# Sheet1.net
KiCad netlist of a schematic drawn in Altium Designer
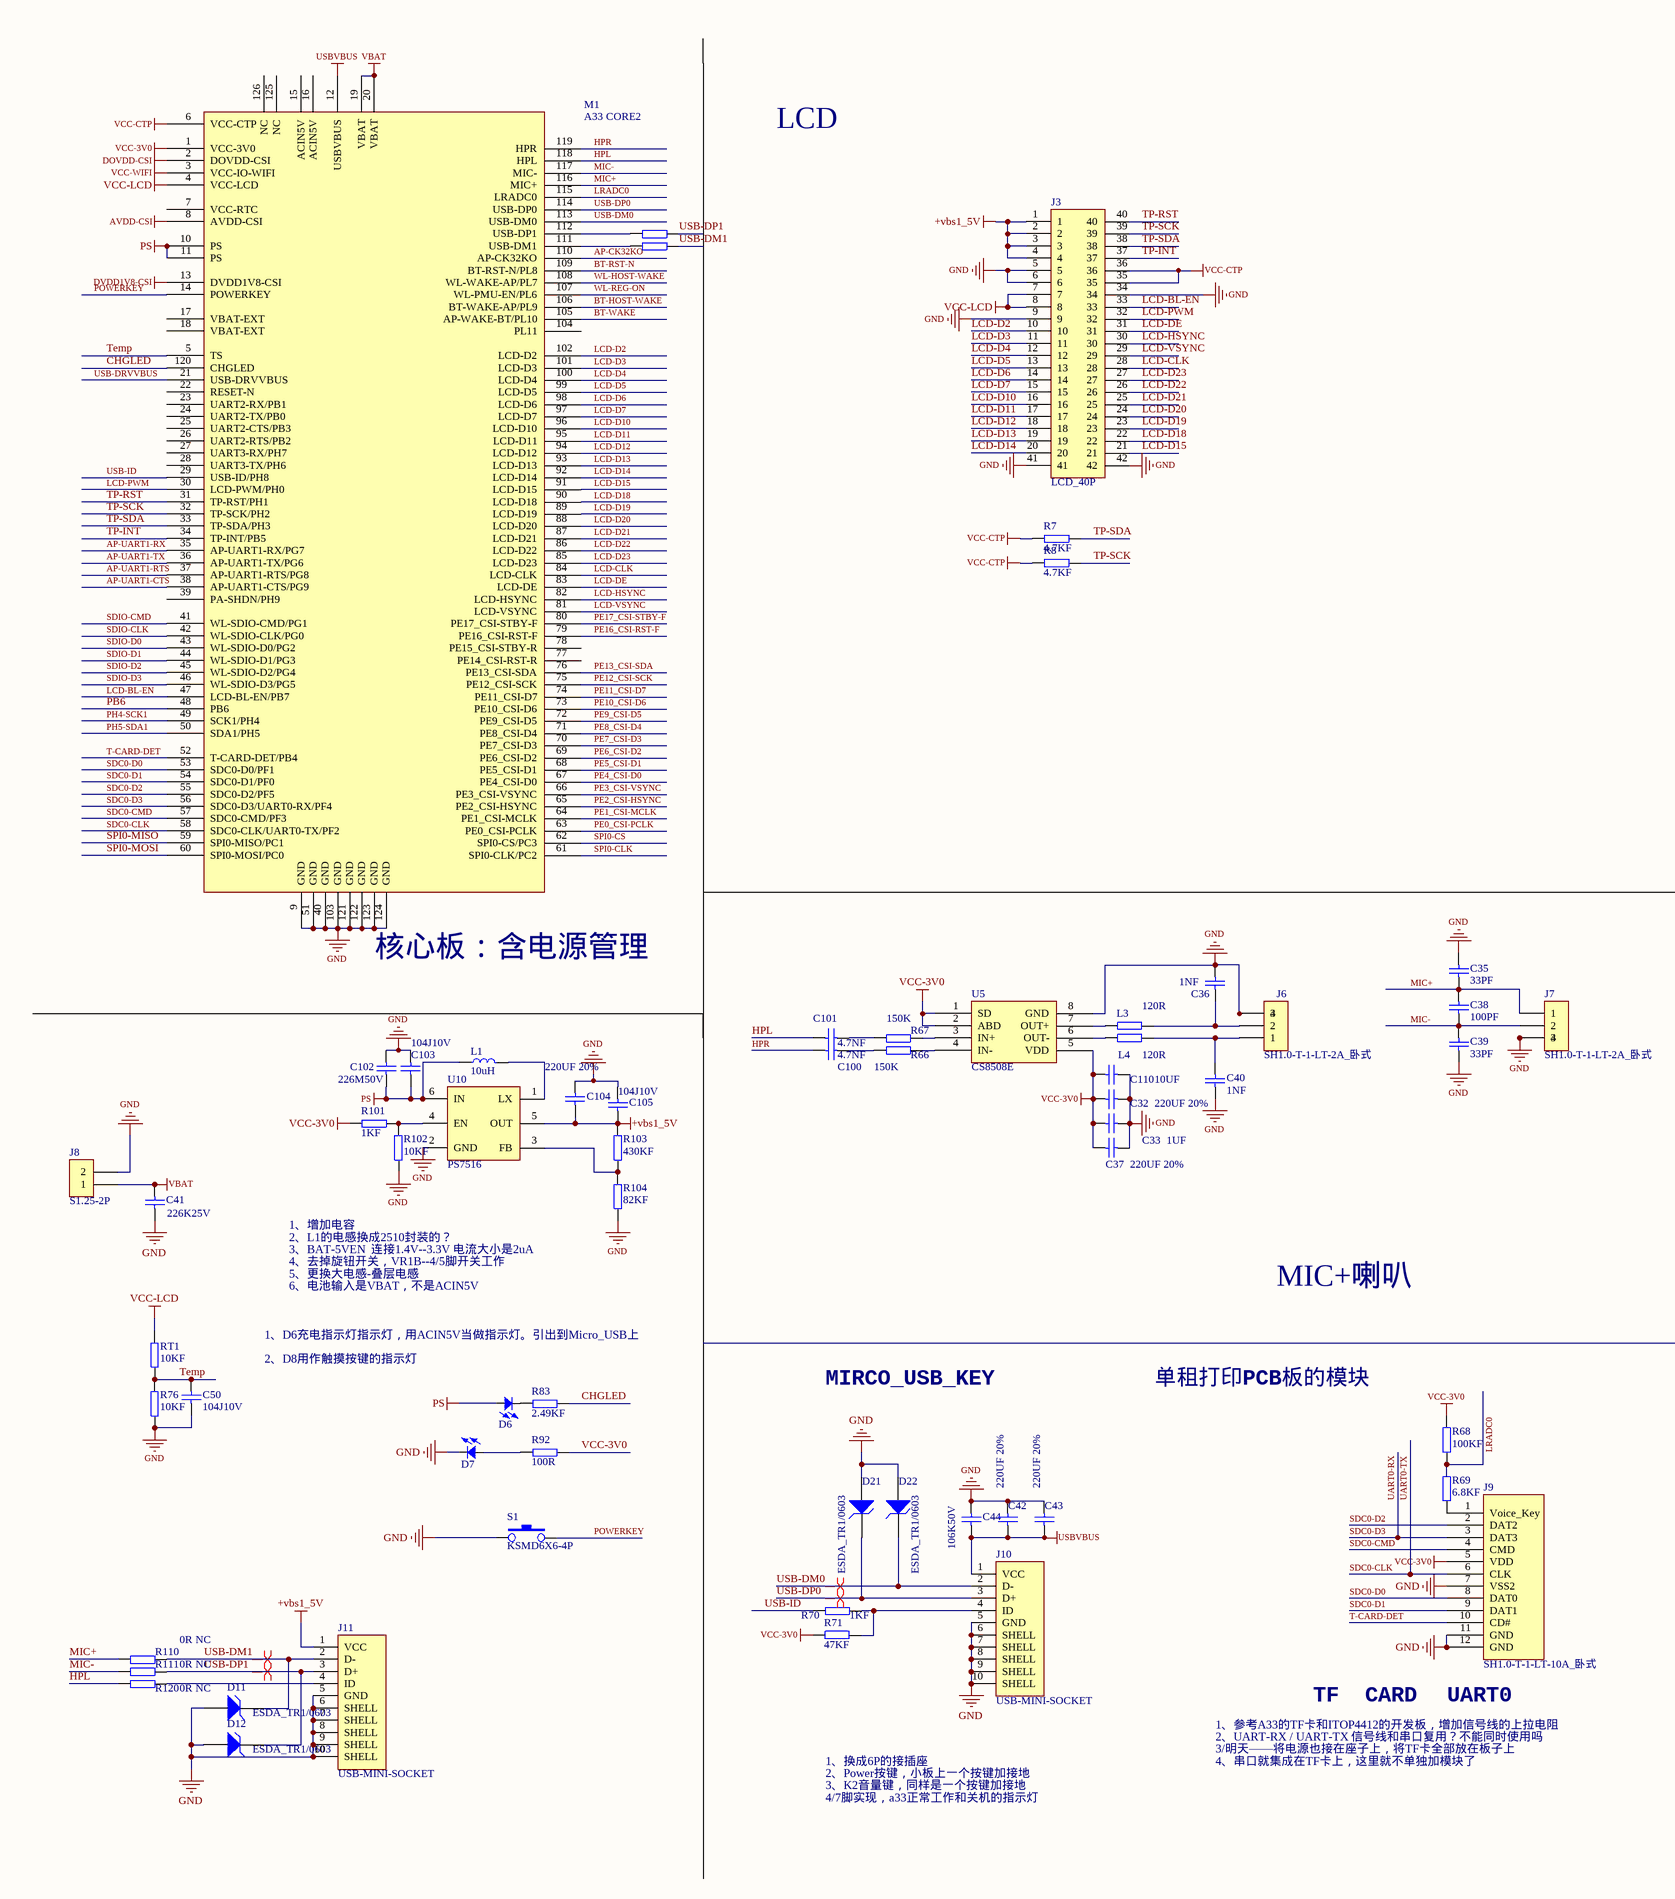
[diagram p0: Sheet1.SchDoc, left]
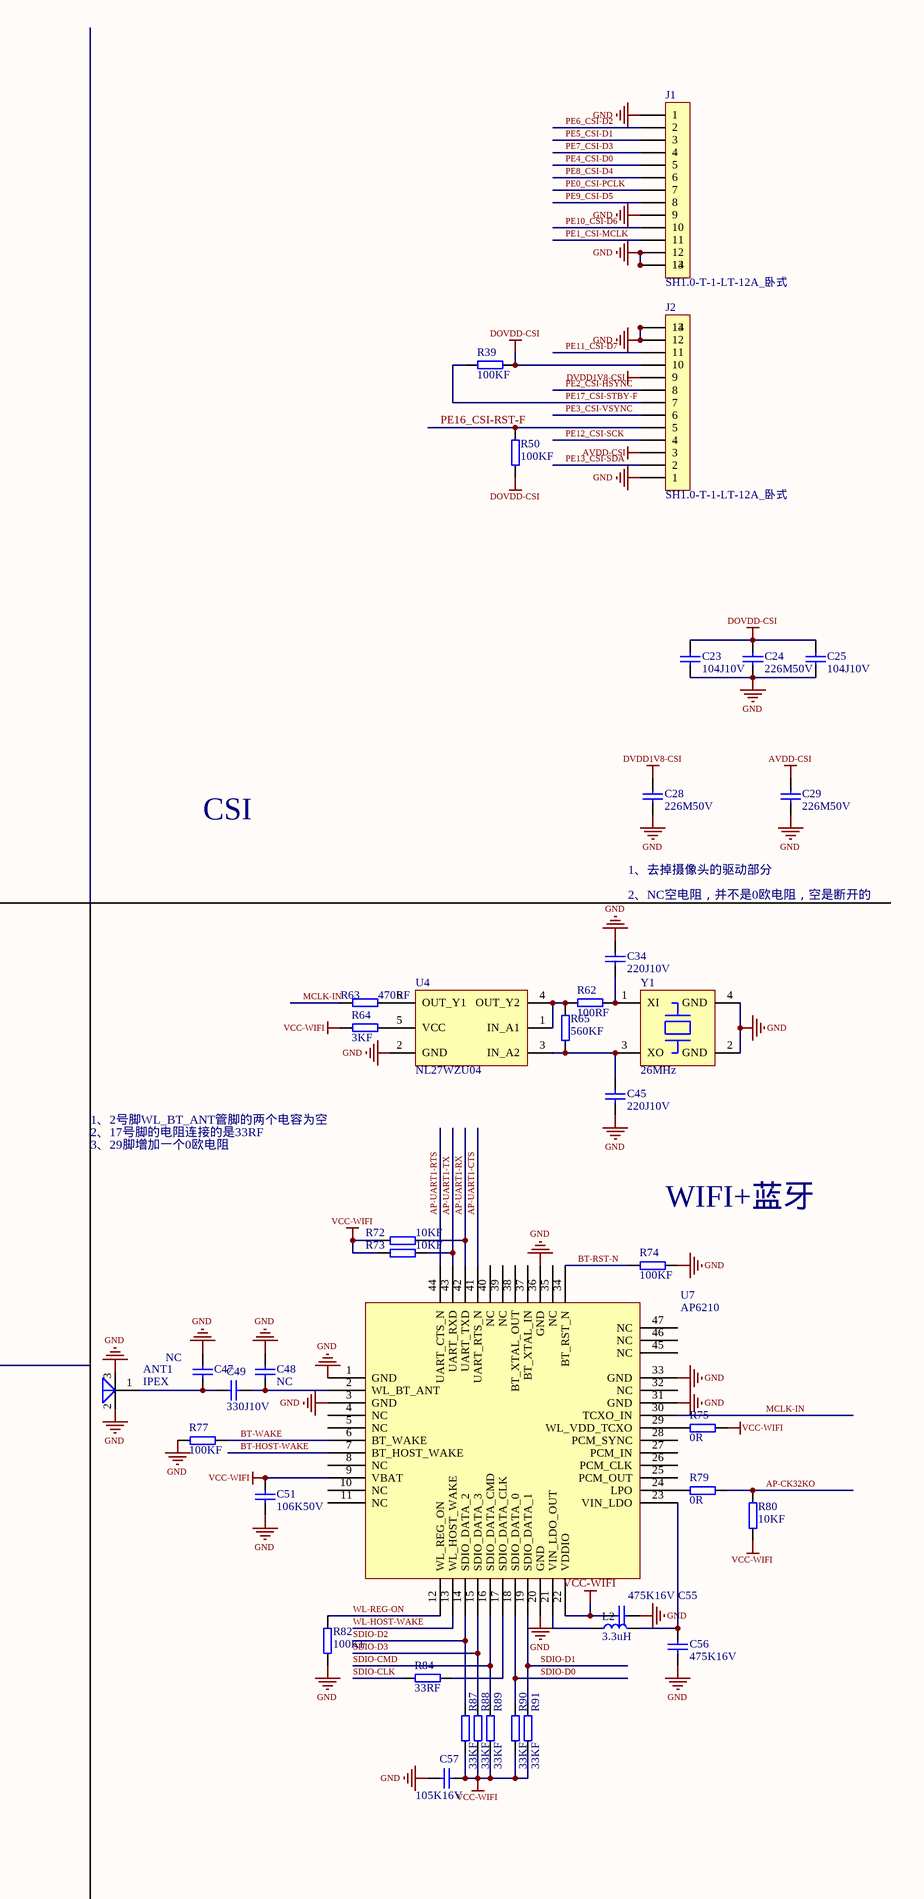
[diagram p1: Sheet1.SchDoc, right]

(export (version "E")
  (design (tool "Eeschema 10.0.6"))
  (components
    (comp (ref "ANT1")
      (value "IPEX")
      (footprint "J-IPEX")
      (description "天线接口IPEX")
      (libsource (lib "Connector") (part "J-IPEX"))
    )
    (comp (ref "C23")
      (value "104J10V")
      (footprint "C0402")
      (description "贴片电容-陶瓷")
      (libsource (lib "Capacitor") (part "C0402X7R-104J10V"))
    )
    (comp (ref "C24")
      (value "226M50V")
      (footprint "C0805")
      (description "贴片电容-陶瓷")
      (libsource (lib "Capacitor") (part "C0805Y5V-226M50V"))
    )
    (comp (ref "C25")
      (value "104J10V")
      (footprint "C0402")
      (description "贴片电容-陶瓷")
      (libsource (lib "Capacitor") (part "C0402X7R-104J10V"))
    )
    (comp (ref "C28")
      (value "226M50V")
      (footprint "C0805")
      (description "贴片电容-陶瓷")
      (libsource (lib "Capacitor") (part "C0805Y5V-226M50V"))
    )
    (comp (ref "C29")
      (value "226M50V")
      (footprint "C0805")
      (description "贴片电容-陶瓷")
      (libsource (lib "Capacitor") (part "C0805Y5V-226M50V"))
    )
    (comp (ref "C32")
      (value "220UF 20%")
      (footprint "C1206")
      (description "C 1206钽电容 --220UF 10V 3216 A型 有极性电容 3.2mm X 1.6mm")
      (libsource (lib "Capacitor") (part "C1206-A型 极性电容"))
    )
    (comp (ref "C33")
      (value "1UF")
      (footprint "C0402")
      (description "贴片电容-陶瓷")
      (libsource (lib "Capacitor") (part "C0402X7R-105J10V"))
    )
    (comp (ref "C34")
      (value "220J10V")
      (footprint "C0402")
      (description "贴片电容-陶瓷")
      (libsource (lib "Capacitor") (part "C0402X7R-220J10V"))
    )
    (comp (ref "C35")
      (value "33PF")
      (footprint "C0402")
      (description "贴片电容-陶瓷")
      (libsource (lib "Capacitor") (part "C0402X7R-104J10V"))
    )
    (comp (ref "C36")
      (value "1NF")
      (footprint "C0402")
      (description "贴片电容-陶瓷")
      (libsource (lib "Capacitor") (part "C0402X7R-220J10V"))
    )
    (comp (ref "C37")
      (value "220UF 20%")
      (footprint "C1206")
      (description "C 1206钽电容 --220UF 10V 3216 A型 有极性电容 3.2mm X 1.6mm")
      (libsource (lib "Capacitor") (part "C1206-A型 极性电容"))
    )
    (comp (ref "C38")
      (value "100PF")
      (footprint "C0402")
      (description "贴片电容-陶瓷")
      (libsource (lib "Capacitor") (part "C0402X7R-104J10V"))
    )
    (comp (ref "C39")
      (value "33PF")
      (footprint "C0402")
      (description "贴片电容-陶瓷")
      (libsource (lib "Capacitor") (part "C0402X7R-104J10V"))
    )
    (comp (ref "C40")
      (value "1NF")
      (footprint "C0402")
      (description "贴片电容-陶瓷")
      (libsource (lib "Capacitor") (part "C0402X7R-220J10V"))
    )
    (comp (ref "C41")
      (value "226K25V")
      (footprint "C0805")
      (description "贴片电容-陶瓷")
      (libsource (lib "Capacitor") (part "C0805X7R-226K25V"))
    )
    (comp (ref "C42")
      (value "220UF 20%")
      (footprint "C1206")
      (description "C 1206钽电容 --220UF 10V 3216 A型 有极性电容 3.2mm X 1.6mm")
      (libsource (lib "Capacitor") (part "C1206-A型 极性电容"))
    )
    (comp (ref "C43")
      (value "220UF 20%")
      (footprint "C1206")
      (description "C 1206钽电容 --220UF 10V 3216 A型 有极性电容 3.2mm X 1.6mm")
      (libsource (lib "Capacitor") (part "C1206-A型 极性电容"))
    )
    (comp (ref "C44")
      (value "106K50V")
      (footprint "C0603")
      (description "贴片电容-陶瓷")
      (libsource (lib "Capacitor") (part "C0603X7R-106K50V"))
    )
    (comp (ref "C45")
      (value "220J10V")
      (footprint "C0402")
      (description "贴片电容-陶瓷")
      (libsource (lib "Capacitor") (part "C0402X7R-220J10V"))
    )
    (comp (ref "C47")
      (value "NC")
      (footprint "C0402")
      (description "贴片电容-陶瓷")
      (libsource (lib "Capacitor") (part "C0402X7R-220J10V"))
    )
    (comp (ref "C48")
      (value "NC")
      (footprint "C0402")
      (description "贴片电容-陶瓷")
      (libsource (lib "Capacitor") (part "C0402X7R-220J10V"))
    )
    (comp (ref "C49")
      (value "330J10V")
      (footprint "C0402")
      (description "贴片电容-陶瓷")
      (libsource (lib "Capacitor") (part "C0402X7R-330J10V"))
    )
    (comp (ref "C50")
      (value "104J10V")
      (footprint "C0402")
      (description "贴片电容-陶瓷")
      (libsource (lib "Capacitor") (part "C0402X7R-104J10V"))
    )
    (comp (ref "C51")
      (value "106K50V")
      (footprint "C0603")
      (description "贴片电容-陶瓷")
      (libsource (lib "Capacitor") (part "C0603X7R-106K50V"))
    )
    (comp (ref "C55")
      (value "475K16V")
      (footprint "C0603")
      (description "贴片电容-陶瓷")
      (libsource (lib "Capacitor") (part "C0603X7R-475K16V"))
    )
    (comp (ref "C56")
      (value "475K16V")
      (footprint "C0603")
      (description "贴片电容-陶瓷")
      (libsource (lib "Capacitor") (part "C0603X7R-475K16V"))
    )
    (comp (ref "C57")
      (value "105K16V")
      (footprint "C0603")
      (description "贴片电容-陶瓷")
      (libsource (lib "Capacitor") (part "C0603X7R-105K16V"))
    )
    (comp (ref "C100")
      (value "4.7NF")
      (footprint "C0603")
      (description "贴片电容-陶瓷")
      (libsource (lib "Capacitor") (part "C0603X7R-330J25V"))
    )
    (comp (ref "C101")
      (value "4.7NF")
      (footprint "C0603")
      (description "贴片电容-陶瓷")
      (libsource (lib "Capacitor") (part "C0603X7R-330J25V"))
    )
    (comp (ref "C102")
      (value "226M50V")
      (footprint "C0805")
      (description "贴片电容-陶瓷")
      (libsource (lib "Capacitor") (part "C0805Y5V-226M50V"))
    )
    (comp (ref "C103")
      (value "104J10V")
      (footprint "C0402")
      (description "贴片电容-陶瓷")
      (libsource (lib "Capacitor") (part "C0402X7R-104J10V"))
    )
    (comp (ref "C104")
      (value "220UF 20%")
      (footprint "C1206")
      (description "C 1206钽电容 --220UF 10V 3216 A型 有极性电容 3.2mm X 1.6mm")
      (libsource (lib "Capacitor") (part "C1206-A型 极性电容"))
    )
    (comp (ref "C105")
      (value "104J10V")
      (footprint "C0402")
      (description "贴片电容-陶瓷")
      (libsource (lib "Capacitor") (part "C0402X7R-104J10V"))
    )
    (comp (ref "C110")
      (value "10UF")
      (footprint "C0603")
      (description "贴片电容-陶瓷")
      (libsource (lib "Capacitor") (part "C0603X7R-330J25V"))
    )
    (comp (ref "D6") (value "发光二极管") (footprint "PCB11:LEDΦ5-H12") (libsource (lib "1_1") (part "发光二极管")))
    (comp (ref "D7") (value "发光二极管") (footprint "PCB11:LEDΦ5-H12") (libsource (lib "1_1") (part "发光二极管")))
    (comp (ref "D11")
      (value "ESDA_TR1/0603")
      (footprint "HS_0603D")
      (description "Zener Diode")
      (fields (field (name "PUBLISHER") "*"))
      (libsource (lib "HSC32K1(QFN56)_BlueTooth_V2.0_20171108 - 副本") (part "D Zener"))
    )
    (comp (ref "D12")
      (value "ESDA_TR1/0603")
      (footprint "HS_0603D")
      (description "Zener Diode")
      (fields (field (name "PUBLISHER") "*"))
      (libsource (lib "HSC32K1(QFN56)_BlueTooth_V2.0_20171108 - 副本") (part "D Zener"))
    )
    (comp (ref "D21")
      (value "ESDA_TR1/0603")
      (footprint "HS_0603D")
      (description "Zener Diode")
      (fields (field (name "PUBLISHER") "*"))
      (libsource (lib "1_1") (part "D Zener"))
    )
    (comp (ref "D22")
      (value "ESDA_TR1/0603")
      (footprint "HS_0603D")
      (description "Zener Diode")
      (fields (field (name "PUBLISHER") "*"))
      (libsource (lib "1_1") (part "D Zener"))
    )
    (comp (ref "J1")
      (value "SH1.0-T-1-LT-12A_卧式")
      (footprint "J-SH1.0-T-1-LT-12A_卧式")
      (libsource (lib "") (part "SH1.0-T-1-LT-12A_卧式_1"))
    )
    (comp (ref "J2")
      (value "SH1.0-T-1-LT-12A_卧式")
      (footprint "J-SH1.0-T-1-LT-12A_卧式")
      (libsource (lib "Connector") (part "SH1.0-T-1-LT-12A_卧式"))
    )
    (comp (ref "J3") (value "LCD_40P") (footprint "LCD P40") (libsource (lib "Connector") (part "LCD_40P")))
    (comp (ref "J6")
      (value "SH1.0-T-1-LT-2A_卧式")
      (footprint "J-SH1.0-T-1-LT-2A_卧式")
      (libsource (lib "") (part "SH1.0-T-1-LT-2A_卧式_1"))
    )
    (comp (ref "J7")
      (value "SH1.0-T-1-LT-2A_卧式")
      (footprint "J-SH1.0-T-1-LT-2A_卧式")
      (libsource (lib "Connector") (part "SH1.0-T-1-LT-2A_卧式"))
    )
    (comp (ref "J8")
      (value "S1.25-2P")
      (footprint "PCB11:S1.25-2P")
      (description "定制铜排")
      (libsource (lib "Others") (part "O-CP-840-2P"))
    )
    (comp (ref "J9")
      (value "SH1.0-T-1-LT-10A_卧式")
      (footprint "J-SH1.0-T-1-LT-10A_卧式")
      (libsource (lib "Connector") (part "SH1.0-T-1-LT-10A_卧式"))
    )
    (comp (ref "J10")
      (value "USB-MINI-SOCKET")
      (footprint "MICRO-USB - 5.9")
      (description "USB-A卧式插座")
      (libsource (lib "Connector") (part "J-USB-MINI-SOCKET"))
    )
    (comp (ref "J11")
      (value "USB-MINI-SOCKET")
      (footprint "MICRO-USB - 5.9")
      (description "USB-A卧式插座")
      (libsource (lib "Connector") (part "J-USB-MINI-SOCKET"))
    )
    (comp (ref "L1")
      (value "10uH")
      (footprint "L-2520")
      (description "贴片电感-层叠")
      (libsource (lib "magnetic") (part "L-2520-10uH"))
    )
    (comp (ref "L2")
      (value "3.3uH")
      (footprint "L0805")
      (description "贴片电感-层叠")
      (libsource (lib "magnetic") (part "L-0805-3.3uH"))
    )
    (comp (ref "L3")
      (value "120R")
      (footprint "R0603")
      (description "贴片电阻-通用")
      (libsource (lib "Resistor") (part "R0603-47KF"))
    )
    (comp (ref "L4")
      (value "120R")
      (footprint "R0603")
      (description "贴片电阻-通用")
      (libsource (lib "Resistor") (part "R0603-47KF"))
    )
    (comp (ref "M1")
      (value "A33 CORE2")
      (footprint "AIWAC-bolster-V02:A33-CORE2")
      (libsource (lib "Module") (part "A33 CORE2"))
    )
    (comp (ref "R7")
      (value "4.7KF")
      (footprint "R0402")
      (description "贴片电阻-通用")
      (libsource (lib "Resistor") (part "R0402-4.7KF"))
    )
    (comp (ref "R8")
      (value "4.7KF")
      (footprint "R0402")
      (description "贴片电阻-通用")
      (libsource (lib "Resistor") (part "R0402-4.7KF"))
    )
    (comp (ref "R39")
      (value "100KF")
      (footprint "R0603")
      (description "贴片电阻-通用")
      (libsource (lib "Resistor") (part "R0603-100KF"))
    )
    (comp (ref "R50")
      (value "100KF")
      (footprint "R0603")
      (description "贴片电阻-通用")
      (libsource (lib "Resistor") (part "R0603-100KF"))
    )
    (comp (ref "R62")
      (value "100RF")
      (footprint "R0603")
      (description "贴片电阻-通用")
      (libsource (lib "Resistor") (part "R0603-100RF"))
    )
    (comp (ref "R63")
      (value "470RF")
      (footprint "R0603")
      (description "贴片电阻-通用")
      (libsource (lib "Resistor") (part "R0603-470RF"))
    )
    (comp (ref "R64")
      (value "3KF")
      (footprint "R0603")
      (description "贴片电阻-通用")
      (libsource (lib "Resistor") (part "R0603-3KF"))
    )
    (comp (ref "R65")
      (value "560KF")
      (footprint "R0603")
      (description "贴片电阻-通用")
      (libsource (lib "Resistor") (part "R0603-560KF"))
    )
    (comp (ref "R66")
      (value "150K")
      (footprint "R0603")
      (description "贴片电阻-通用")
      (libsource (lib "Resistor") (part "R0603-10KF"))
    )
    (comp (ref "R67")
      (value "150K")
      (footprint "R0603")
      (description "贴片电阻-通用")
      (libsource (lib "Resistor") (part "R0603-10KF"))
    )
    (comp (ref "R68")
      (value "100KF")
      (footprint "R0603")
      (description "贴片电阻-通用")
      (libsource (lib "Resistor") (part "R0603-100KF"))
    )
    (comp (ref "R69")
      (value "6.8KF")
      (footprint "R0603")
      (description "贴片电阻-通用")
      (libsource (lib "Resistor") (part "R0603-6.8KF"))
    )
    (comp (ref "R70")
      (value "1KF")
      (footprint "R0603")
      (description "贴片电阻-通用")
      (libsource (lib "Resistor") (part "R0603-1KF"))
    )
    (comp (ref "R71")
      (value "47KF")
      (footprint "R0603")
      (description "贴片电阻-通用")
      (libsource (lib "Resistor") (part "R0603-47KF"))
    )
    (comp (ref "R72")
      (value "10KF")
      (footprint "R0603")
      (description "贴片电阻-通用")
      (libsource (lib "Resistor") (part "R0603-10KF"))
    )
    (comp (ref "R73")
      (value "10KF")
      (footprint "R0603")
      (description "贴片电阻-通用")
      (libsource (lib "Resistor") (part "R0603-10KF"))
    )
    (comp (ref "R74")
      (value "100KF")
      (footprint "R0603")
      (description "贴片电阻-通用")
      (libsource (lib "Resistor") (part "R0603-100KF"))
    )
    (comp (ref "R75")
      (value "0R")
      (footprint "R0603")
      (description "贴片电阻-通用")
      (libsource (lib "Resistor") (part "R0603-0R"))
    )
    (comp (ref "R76")
      (value "10KF")
      (footprint "R0603")
      (description "贴片电阻-通用")
      (libsource (lib "Resistor") (part "R0603-10KF"))
    )
    (comp (ref "R77")
      (value "100KF")
      (footprint "R0603")
      (description "贴片电阻-通用")
      (libsource (lib "Resistor") (part "R0603-100KF"))
    )
    (comp (ref "R79")
      (value "0R")
      (footprint "R0603")
      (description "贴片电阻-通用")
      (libsource (lib "Resistor") (part "R0603-0R"))
    )
    (comp (ref "R80")
      (value "10KF")
      (footprint "R0603")
      (description "贴片电阻-通用")
      (libsource (lib "Resistor") (part "R0603-10KF"))
    )
    (comp (ref "R82")
      (value "100KF")
      (footprint "R0603")
      (description "贴片电阻-通用")
      (libsource (lib "Resistor") (part "R0603-100KF"))
    )
    (comp (ref "R83")
      (value "2.49KF")
      (footprint "R0603")
      (description "贴片电阻-通用")
      (libsource (lib "Resistor") (part "R0603-3KF"))
    )
    (comp (ref "R84")
      (value "33RF")
      (footprint "R0603")
      (description "贴片电阻-通用")
      (libsource (lib "Resistor") (part "R0603-33RF"))
    )
    (comp (ref "R87")
      (value "33KF")
      (footprint "R0603")
      (description "贴片电阻-通用")
      (libsource (lib "Resistor") (part "R0603-33KF"))
    )
    (comp (ref "R88")
      (value "33KF")
      (footprint "R0603")
      (description "贴片电阻-通用")
      (libsource (lib "Resistor") (part "R0603-33KF"))
    )
    (comp (ref "R89")
      (value "33KF")
      (footprint "R0603")
      (description "贴片电阻-通用")
      (libsource (lib "Resistor") (part "R0603-33KF"))
    )
    (comp (ref "R90")
      (value "33KF")
      (footprint "R0603")
      (description "贴片电阻-通用")
      (libsource (lib "Resistor") (part "R0603-33KF"))
    )
    (comp (ref "R91")
      (value "33KF")
      (footprint "R0603")
      (description "贴片电阻-通用")
      (libsource (lib "Resistor") (part "R0603-33KF"))
    )
    (comp (ref "R92")
      (value "100R")
      (footprint "R0603")
      (description "贴片电阻-通用")
      (libsource (lib "Resistor") (part "R0603-2KF"))
    )
    (comp (ref "R101")
      (value "1KF")
      (footprint "R0603")
      (description "贴片电阻-通用")
      (libsource (lib "Resistor") (part "R0603-1KF"))
    )
    (comp (ref "R102")
      (value "10KF")
      (footprint "R0603")
      (description "贴片电阻-通用")
      (libsource (lib "Resistor") (part "R0603-10KF"))
    )
    (comp (ref "R103")
      (value "430KF")
      (footprint "R0603")
      (description "贴片电阻-通用")
      (libsource (lib "Resistor") (part "R0603-430KF"))
    )
    (comp (ref "R104")
      (value "82KF")
      (footprint "R0603")
      (description "贴片电阻-通用")
      (libsource (lib "Resistor") (part "R0603-82KF"))
    )
    (comp (ref "R110")
      (value "0R NC")
      (footprint "R0603")
      (description "贴片电阻-通用")
      (libsource (lib "Resistor") (part "R0603-2KF"))
    )
    (comp (ref "R111")
      (value "0R NC")
      (footprint "R0603")
      (description "贴片电阻-通用")
      (libsource (lib "Resistor") (part "R0603-2KF"))
    )
    (comp (ref "R112")
      (value "0R  NC")
      (footprint "R0603")
      (description "贴片电阻-通用")
      (libsource (lib "Resistor") (part "R0603-10KF"))
    )
    (comp (ref "R113")
      (value "0R  NC")
      (footprint "R0603")
      (description "贴片电阻-通用")
      (libsource (lib "Resistor") (part "R0603-10KF"))
    )
    (comp (ref "R120")
      (value "0R NC")
      (footprint "R0603")
      (description "贴片电阻-通用")
      (libsource (lib "Resistor") (part "R0603-2KF"))
    )
    (comp (ref "RT1")
      (value "10KF")
      (footprint "XU-GENARAL PCB :0402")
      (description "贴片电阻-通用")
      (libsource (lib "Resistor") (part "R0603-10KF"))
    )
    (comp (ref "S1")
      (value "KSMD6X6-4P")
      (footprint "PCB11:SW2-6*6H")
      (description "轻触按键")
      (libsource (lib "Key") (part "S-KSMD6X6-4P"))
    )
    (comp (ref "U4") (value "NL27WZU04") (footprint "U-TSOP-6") (libsource (lib "IC") (part "NL27WZU04")))
    (comp (ref "U5") (value "CS8508E") (footprint "SO-8") (libsource (lib "PCB_Project_1") (part "CS8508E")))
    (comp (ref "U7")
      (value "AP6210")
      (footprint "AIWAC-bolster-V02:AP6210")
      (libsource (lib "IC") (part "AP6210"))
    )
    (comp (ref "U10") (value "PS7516") (footprint "U-SOT-23-6") (libsource (lib "IC") (part "PS7516")))
    (comp (ref "Y1")
      (value "26MHz")
      (footprint "Y-CPX-32GA-4P")
      (description "晶振-贴片无源")
      (libsource (lib "Others") (part "YC-26MHz"))
    )
  )
  (nets
    (net (code "1") (name "+vbs1_5V") (class "Default")
      (node (ref "C104") (pin "1") (pinfunction "1_1") (pintype "passive"))
      (node (ref "C105") (pin "2") (pinfunction "2_2") (pintype "passive"))
      (node (ref "J11") (pin "1") (pinfunction "VCC_1") (pintype "passive"))
      (node (ref "J3") (pin "1") (pinfunction "1_1") (pintype "passive"))
      (node (ref "J3") (pin "2") (pinfunction "2_2") (pintype "passive"))
      (node (ref "J3") (pin "3") (pinfunction "3_3") (pintype "passive"))
      (node (ref "J3") (pin "4") (pinfunction "4_4") (pintype "passive"))
      (node (ref "R103") (pin "2") (pinfunction "2_2") (pintype "passive"))
      (node (ref "U10") (pin "5") (pinfunction "OUT_5") (pintype "passive"))
    )
    (net (code "2") (name "/AP-CK32KO") (class "Default")
      (node (ref "M1") (pin "110") (pinfunction "AP-CK32KO_110") (pintype "passive"))
      (node (ref "R79") (pin "2") (pinfunction "2_2") (pintype "passive"))
      (node (ref "R80") (pin "2") (pinfunction "2_2") (pintype "passive"))
    )
    (net (code "3") (name "/AP-UART1-CTS") (class "Default")
      (node (ref "M1") (pin "38") (pinfunction "AP-UART1-CTS/PG9_38") (pintype "passive"))
      (node (ref "U7") (pin "41") (pinfunction "UART_RTS_N_41") (pintype "passive"))
    )
    (net (code "4") (name "/AP-UART1-RTS") (class "Default")
      (node (ref "M1") (pin "37") (pinfunction "AP-UART1-RTS/PG8_37") (pintype "passive"))
      (node (ref "U7") (pin "44") (pinfunction "UART_CTS_N_44") (pintype "passive"))
    )
    (net (code "5") (name "/AP-UART1-RX") (class "Default")
      (node (ref "M1") (pin "35") (pinfunction "AP-UART1-RX/PG7_35") (pintype "passive"))
      (node (ref "R72") (pin "2") (pinfunction "2_2") (pintype "passive"))
      (node (ref "U7") (pin "42") (pinfunction "UART_TXD_42") (pintype "passive"))
    )
    (net (code "6") (name "/AP-UART1-TX") (class "Default")
      (node (ref "M1") (pin "36") (pinfunction "AP-UART1-TX/PG6_36") (pintype "passive"))
      (node (ref "R73") (pin "2") (pinfunction "2_2") (pintype "passive"))
      (node (ref "U7") (pin "43") (pinfunction "UART_RXD_43") (pintype "passive"))
    )
    (net (code "7") (name "/BT-HOST-WAKE") (class "Default")
      (node (ref "M1") (pin "106") (pinfunction "BT-WAKE-AP/PL9_106") (pintype "passive"))
      (node (ref "U7") (pin "7") (pinfunction "BT_HOST_WAKE_7") (pintype "passive"))
    )
    (net (code "8") (name "/BT-RST-N") (class "Default")
      (node (ref "M1") (pin "109") (pinfunction "BT-RST-N/PL8_109") (pintype "passive"))
      (node (ref "R74") (pin "1") (pinfunction "1_1") (pintype "passive"))
      (node (ref "U7") (pin "34") (pinfunction "BT_RST_N_34") (pintype "passive"))
    )
    (net (code "9") (name "/BT-WAKE") (class "Default")
      (node (ref "M1") (pin "105") (pinfunction "AP-WAKE-BT/PL10_105") (pintype "passive"))
      (node (ref "R77") (pin "1") (pinfunction "1_1") (pintype "passive"))
      (node (ref "U7") (pin "6") (pinfunction "BT_WAKE_6") (pintype "passive"))
    )
    (net (code "10") (name "/CHGLED") (class "Default")
      (node (ref "M1") (pin "120") (pinfunction "CHGLED_120") (pintype "passive"))
      (node (ref "R83") (pin "2") (pinfunction "2_2") (pintype "passive"))
    )
    (net (code "11") (name "/HPL") (class "Default")
      (node (ref "C101") (pin "1") (pinfunction "1_1") (pintype "passive"))
      (node (ref "M1") (pin "118") (pinfunction "HPL_118") (pintype "passive"))
      (node (ref "R120") (pin "1") (pinfunction "1_1") (pintype "passive"))
    )
    (net (code "12") (name "/HPR") (class "Default")
      (node (ref "C100") (pin "1") (pinfunction "1_1") (pintype "passive"))
      (node (ref "M1") (pin "119") (pinfunction "HPR_119") (pintype "passive"))
    )
    (net (code "13") (name "/LCD-BL-EN") (class "Default")
      (node (ref "J3") (pin "33") (pinfunction "33_33") (pintype "passive"))
      (node (ref "M1") (pin "47") (pinfunction "LCD-BL-EN/PB7_47") (pintype "passive"))
    )
    (net (code "14") (name "/LCD-CLK") (class "Default")
      (node (ref "J3") (pin "28") (pinfunction "28_28") (pintype "passive"))
      (node (ref "M1") (pin "84") (pinfunction "LCD-CLK_84") (pintype "passive"))
    )
    (net (code "15") (name "/LCD-D2") (class "Default")
      (node (ref "J3") (pin "10") (pinfunction "10_10") (pintype "passive"))
      (node (ref "M1") (pin "102") (pinfunction "LCD-D2_102") (pintype "passive"))
    )
    (net (code "16") (name "/LCD-D3") (class "Default")
      (node (ref "J3") (pin "11") (pinfunction "11_11") (pintype "passive"))
      (node (ref "M1") (pin "101") (pinfunction "LCD-D3_101") (pintype "passive"))
    )
    (net (code "17") (name "/LCD-D4") (class "Default")
      (node (ref "J3") (pin "12") (pinfunction "12_12") (pintype "passive"))
      (node (ref "M1") (pin "100") (pinfunction "LCD-D4_100") (pintype "passive"))
    )
    (net (code "18") (name "/LCD-D5") (class "Default")
      (node (ref "J3") (pin "13") (pinfunction "13_13") (pintype "passive"))
      (node (ref "M1") (pin "99") (pinfunction "LCD-D5_99") (pintype "passive"))
    )
    (net (code "19") (name "/LCD-D6") (class "Default")
      (node (ref "J3") (pin "14") (pinfunction "14_14") (pintype "passive"))
      (node (ref "M1") (pin "98") (pinfunction "LCD-D6_98") (pintype "passive"))
    )
    (net (code "20") (name "/LCD-D7") (class "Default")
      (node (ref "J3") (pin "15") (pinfunction "15_15") (pintype "passive"))
      (node (ref "M1") (pin "97") (pinfunction "LCD-D7_97") (pintype "passive"))
    )
    (net (code "21") (name "/LCD-D10") (class "Default")
      (node (ref "J3") (pin "16") (pinfunction "16_16") (pintype "passive"))
      (node (ref "M1") (pin "96") (pinfunction "LCD-D10_96") (pintype "passive"))
    )
    (net (code "22") (name "/LCD-D11") (class "Default")
      (node (ref "J3") (pin "17") (pinfunction "17_17") (pintype "passive"))
      (node (ref "M1") (pin "95") (pinfunction "LCD-D11_95") (pintype "passive"))
    )
    (net (code "23") (name "/LCD-D12") (class "Default")
      (node (ref "J3") (pin "18") (pinfunction "18_18") (pintype "passive"))
      (node (ref "M1") (pin "94") (pinfunction "LCD-D12_94") (pintype "passive"))
    )
    (net (code "24") (name "/LCD-D13") (class "Default")
      (node (ref "J3") (pin "19") (pinfunction "19_19") (pintype "passive"))
      (node (ref "M1") (pin "93") (pinfunction "LCD-D13_93") (pintype "passive"))
    )
    (net (code "25") (name "/LCD-D14") (class "Default")
      (node (ref "J3") (pin "20") (pinfunction "20_20") (pintype "passive"))
      (node (ref "M1") (pin "92") (pinfunction "LCD-D14_92") (pintype "passive"))
    )
    (net (code "26") (name "/LCD-D15") (class "Default")
      (node (ref "J3") (pin "21") (pinfunction "21_21") (pintype "passive"))
      (node (ref "M1") (pin "91") (pinfunction "LCD-D15_91") (pintype "passive"))
    )
    (net (code "27") (name "/LCD-D18") (class "Default")
      (node (ref "J3") (pin "22") (pinfunction "22_22") (pintype "passive"))
      (node (ref "M1") (pin "90") (pinfunction "LCD-D18_90") (pintype "passive"))
    )
    (net (code "28") (name "/LCD-D19") (class "Default")
      (node (ref "J3") (pin "23") (pinfunction "23_23") (pintype "passive"))
      (node (ref "M1") (pin "89") (pinfunction "LCD-D19_89") (pintype "passive"))
    )
    (net (code "29") (name "/LCD-D20") (class "Default")
      (node (ref "J3") (pin "24") (pinfunction "24_24") (pintype "passive"))
      (node (ref "M1") (pin "88") (pinfunction "LCD-D20_88") (pintype "passive"))
    )
    (net (code "30") (name "/LCD-D21") (class "Default")
      (node (ref "J3") (pin "25") (pinfunction "25_25") (pintype "passive"))
      (node (ref "M1") (pin "87") (pinfunction "LCD-D21_87") (pintype "passive"))
    )
    (net (code "31") (name "/LCD-D22") (class "Default")
      (node (ref "J3") (pin "26") (pinfunction "26_26") (pintype "passive"))
      (node (ref "M1") (pin "86") (pinfunction "LCD-D22_86") (pintype "passive"))
    )
    (net (code "32") (name "/LCD-D23") (class "Default")
      (node (ref "J3") (pin "27") (pinfunction "27_27") (pintype "passive"))
      (node (ref "M1") (pin "85") (pinfunction "LCD-D23_85") (pintype "passive"))
    )
    (net (code "33") (name "/LCD-DE") (class "Default")
      (node (ref "J3") (pin "31") (pinfunction "31_31") (pintype "passive"))
      (node (ref "M1") (pin "83") (pinfunction "LCD-DE_83") (pintype "passive"))
    )
    (net (code "34") (name "/LCD-HSYNC") (class "Default")
      (node (ref "J3") (pin "30") (pinfunction "30_30") (pintype "passive"))
      (node (ref "M1") (pin "82") (pinfunction "LCD-HSYNC_82") (pintype "passive"))
    )
    (net (code "35") (name "/LCD-PWM") (class "Default")
      (node (ref "J3") (pin "32") (pinfunction "32_32") (pintype "passive"))
      (node (ref "M1") (pin "30") (pinfunction "LCD-PWM/PH0_30") (pintype "passive"))
    )
    (net (code "36") (name "/LCD-VSYNC") (class "Default")
      (node (ref "J3") (pin "29") (pinfunction "29_29") (pintype "passive"))
      (node (ref "M1") (pin "81") (pinfunction "LCD-VSYNC_81") (pintype "passive"))
    )
    (net (code "37") (name "/LRADC0") (class "Default")
      (node (ref "M1") (pin "115") (pinfunction "LRADC0_115") (pintype "passive"))
      (node (ref "R68") (pin "2") (pinfunction "2_2") (pintype "passive"))
      (node (ref "R69") (pin "1") (pinfunction "1_1") (pintype "passive"))
    )
    (net (code "38") (name "/MCLK-IN") (class "Default")
      (node (ref "R63") (pin "1") (pinfunction "1_1") (pintype "passive"))
      (node (ref "U7") (pin "30") (pinfunction "TCXO_IN_30") (pintype "passive"))
    )
    (net (code "39") (name "/MIC+") (class "Default")
      (node (ref "C35") (pin "2") (pinfunction "2_2") (pintype "passive"))
      (node (ref "C38") (pin "1") (pinfunction "1_1") (pintype "passive"))
      (node (ref "J7") (pin "1") (pinfunction "1_1") (pintype "passive"))
      (node (ref "M1") (pin "116") (pinfunction "MIC+_116") (pintype "passive"))
      (node (ref "R110") (pin "1") (pinfunction "1_1") (pintype "passive"))
    )
    (net (code "40") (name "/MIC-") (class "Default")
      (node (ref "C38") (pin "2") (pinfunction "2_2") (pintype "passive"))
      (node (ref "C39") (pin "1") (pinfunction "1_1") (pintype "passive"))
      (node (ref "J7") (pin "2") (pinfunction "2_2") (pintype "passive"))
      (node (ref "M1") (pin "117") (pinfunction "MIC-_117") (pintype "passive"))
      (node (ref "R111") (pin "1") (pinfunction "1_1") (pintype "passive"))
    )
    (net (code "41") (name "/PB6") (class "Default")
      (node (ref "M1") (pin "48") (pinfunction "PB6_48") (pintype "passive"))
    )
    (net (code "42") (name "/PE0_CSI-PCLK") (class "Default")
      (node (ref "J1") (pin "7") (pinfunction "7_7") (pintype "passive"))
      (node (ref "M1") (pin "63") (pinfunction "PE0_CSI-PCLK_63") (pintype "passive"))
    )
    (net (code "43") (name "/PE1_CSI-MCLK") (class "Default")
      (node (ref "J1") (pin "11") (pinfunction "11_11") (pintype "passive"))
      (node (ref "M1") (pin "64") (pinfunction "PE1_CSI-MCLK_64") (pintype "passive"))
    )
    (net (code "44") (name "/PE2_CSI-HSYNC") (class "Default")
      (node (ref "J2") (pin "8") (pinfunction "8_8") (pintype "passive"))
      (node (ref "M1") (pin "65") (pinfunction "PE2_CSI-HSYNC_65") (pintype "passive"))
    )
    (net (code "45") (name "/PE3_CSI-VSYNC") (class "Default")
      (node (ref "J2") (pin "6") (pinfunction "6_6") (pintype "passive"))
      (node (ref "M1") (pin "66") (pinfunction "PE3_CSI-VSYNC_66") (pintype "passive"))
    )
    (net (code "46") (name "/PE4_CSI-D0") (class "Default")
      (node (ref "J1") (pin "5") (pinfunction "5_5") (pintype "passive"))
      (node (ref "M1") (pin "67") (pinfunction "PE4_CSI-D0_67") (pintype "passive"))
    )
    (net (code "47") (name "/PE5_CSI-D1") (class "Default")
      (node (ref "J1") (pin "3") (pinfunction "3_3") (pintype "passive"))
      (node (ref "M1") (pin "68") (pinfunction "PE5_CSI-D1_68") (pintype "passive"))
    )
    (net (code "48") (name "/PE6_CSI-D2") (class "Default")
      (node (ref "J1") (pin "2") (pinfunction "2_2") (pintype "passive"))
      (node (ref "M1") (pin "69") (pinfunction "PE6_CSI-D2_69") (pintype "passive"))
    )
    (net (code "49") (name "/PE7_CSI-D3") (class "Default")
      (node (ref "J1") (pin "4") (pinfunction "4_4") (pintype "passive"))
      (node (ref "M1") (pin "70") (pinfunction "PE7_CSI-D3_70") (pintype "passive"))
    )
    (net (code "50") (name "/PE8_CSI-D4") (class "Default")
      (node (ref "J1") (pin "6") (pinfunction "6_6") (pintype "passive"))
      (node (ref "M1") (pin "71") (pinfunction "PE8_CSI-D4_71") (pintype "passive"))
    )
    (net (code "51") (name "/PE9_CSI-D5") (class "Default")
      (node (ref "J1") (pin "8") (pinfunction "8_8") (pintype "passive"))
      (node (ref "M1") (pin "72") (pinfunction "PE9_CSI-D5_72") (pintype "passive"))
    )
    (net (code "52") (name "/PE10_CSI-D6") (class "Default")
      (node (ref "J1") (pin "10") (pinfunction "10_10") (pintype "passive"))
      (node (ref "M1") (pin "73") (pinfunction "PE10_CSI-D6_73") (pintype "passive"))
    )
    (net (code "53") (name "/PE11_CSI-D7") (class "Default")
      (node (ref "J2") (pin "11") (pinfunction "11_11") (pintype "passive"))
      (node (ref "M1") (pin "74") (pinfunction "PE11_CSI-D7_74") (pintype "passive"))
    )
    (net (code "54") (name "/PE12_CSI-SCK") (class "Default")
      (node (ref "J2") (pin "4") (pinfunction "4_4") (pintype "passive"))
      (node (ref "M1") (pin "75") (pinfunction "PE12_CSI-SCK_75") (pintype "passive"))
    )
    (net (code "55") (name "/PE13_CSI-SDA") (class "Default")
      (node (ref "J2") (pin "2") (pinfunction "2_2") (pintype "passive"))
      (node (ref "M1") (pin "76") (pinfunction "PE13_CSI-SDA_76") (pintype "passive"))
    )
    (net (code "56") (name "/PE16_CSI-RST-F") (class "Default")
      (node (ref "J2") (pin "5") (pinfunction "5_5") (pintype "passive"))
      (node (ref "M1") (pin "79") (pinfunction "PE16_CSI-RST-F_79") (pintype "passive"))
      (node (ref "R50") (pin "2") (pinfunction "2_2") (pintype "passive"))
    )
    (net (code "57") (name "/PE17_CSI-STBY-F") (class "Default")
      (node (ref "J2") (pin "7") (pinfunction "7_7") (pintype "passive"))
      (node (ref "M1") (pin "80") (pinfunction "PE17_CSI-STBY-F_80") (pintype "passive"))
      (node (ref "R39") (pin "1") (pinfunction "1_1") (pintype "passive"))
    )
    (net (code "58") (name "/PH4-SCK1") (class "Default")
      (node (ref "M1") (pin "49") (pinfunction "SCK1/PH4_49") (pintype "passive"))
    )
    (net (code "59") (name "/PH5-SDA1") (class "Default")
      (node (ref "M1") (pin "50") (pinfunction "SDA1/PH5_50") (pintype "passive"))
    )
    (net (code "60") (name "/POWERKEY") (class "Default")
      (node (ref "M1") (pin "14") (pinfunction "POWERKEY_14") (pintype "passive"))
      (node (ref "S1") (pin "2") (pinfunction "2_2") (pintype "passive"))
    )
    (net (code "61") (name "/SDC0-CLK") (class "Default")
      (node (ref "J9") (pin "6") (pinfunction "CLK_6") (pintype "passive"))
      (node (ref "M1") (pin "58") (pinfunction "SDC0-CLK/UART0-TX/PF2_58") (pintype "passive"))
    )
    (net (code "62") (name "/SDC0-CMD") (class "Default")
      (node (ref "J9") (pin "4") (pinfunction "CMD_4") (pintype "power_in"))
      (node (ref "M1") (pin "57") (pinfunction "SDC0-CMD/PF3_57") (pintype "passive"))
    )
    (net (code "63") (name "/SDC0-D0") (class "Default")
      (node (ref "J9") (pin "8") (pinfunction "DAT0_8") (pintype "passive"))
      (node (ref "M1") (pin "53") (pinfunction "SDC0-D0/PF1_53") (pintype "passive"))
    )
    (net (code "64") (name "/SDC0-D1") (class "Default")
      (node (ref "J9") (pin "9") (pinfunction "DAT1_9") (pintype "passive"))
      (node (ref "M1") (pin "54") (pinfunction "SDC0-D1/PF0_54") (pintype "passive"))
    )
    (net (code "65") (name "/SDC0-D2") (class "Default")
      (node (ref "J9") (pin "2") (pinfunction "DAT2_2") (pintype "power_in"))
      (node (ref "M1") (pin "55") (pinfunction "SDC0-D2/PF5_55") (pintype "passive"))
    )
    (net (code "66") (name "/SDC0-D3") (class "Default")
      (node (ref "J9") (pin "3") (pinfunction "DAT3_3") (pintype "power_in"))
      (node (ref "M1") (pin "56") (pinfunction "SDC0-D3/UART0-RX/PF4_56") (pintype "passive"))
    )
    (net (code "67") (name "/SDIO-CLK") (class "Default")
      (node (ref "M1") (pin "42") (pinfunction "WL-SDIO-CLK/PG0_42") (pintype "passive"))
      (node (ref "R84") (pin "2") (pinfunction "2_2") (pintype "passive"))
    )
    (net (code "68") (name "/SDIO-CMD") (class "Default")
      (node (ref "M1") (pin "41") (pinfunction "WL-SDIO-CMD/PG1_41") (pintype "passive"))
      (node (ref "R89") (pin "2") (pinfunction "2_2") (pintype "passive"))
      (node (ref "U7") (pin "16") (pinfunction "SDIO_DATA_CMD_16") (pintype "passive"))
    )
    (net (code "69") (name "/SDIO-D0") (class "Default")
      (node (ref "M1") (pin "43") (pinfunction "WL-SDIO-D0/PG2_43") (pintype "passive"))
      (node (ref "R90") (pin "2") (pinfunction "2_2") (pintype "passive"))
      (node (ref "U7") (pin "18") (pinfunction "SDIO_DATA_0_18") (pintype "passive"))
    )
    (net (code "70") (name "/SDIO-D1") (class "Default")
      (node (ref "M1") (pin "44") (pinfunction "WL-SDIO-D1/PG3_44") (pintype "passive"))
      (node (ref "R91") (pin "2") (pinfunction "2_2") (pintype "passive"))
      (node (ref "U7") (pin "19") (pinfunction "SDIO_DATA_1_19") (pintype "passive"))
    )
    (net (code "71") (name "/SDIO-D2") (class "Default")
      (node (ref "M1") (pin "45") (pinfunction "WL-SDIO-D2/PG4_45") (pintype "passive"))
      (node (ref "R87") (pin "2") (pinfunction "2_2") (pintype "passive"))
      (node (ref "U7") (pin "14") (pinfunction "SDIO_DATA_2_14") (pintype "passive"))
    )
    (net (code "72") (name "/SDIO-D3") (class "Default")
      (node (ref "M1") (pin "46") (pinfunction "WL-SDIO-D3/PG5_46") (pintype "passive"))
      (node (ref "R88") (pin "2") (pinfunction "2_2") (pintype "passive"))
      (node (ref "U7") (pin "15") (pinfunction "SDIO_DATA_3_15") (pintype "passive"))
    )
    (net (code "73") (name "/SPI0-CLK") (class "Default")
      (node (ref "M1") (pin "61") (pinfunction "SPI0-CLK/PC2_61") (pintype "passive"))
    )
    (net (code "74") (name "/SPI0-CS") (class "Default")
      (node (ref "M1") (pin "62") (pinfunction "SPI0-CS/PC3_62") (pintype "passive"))
    )
    (net (code "75") (name "/SPI0-MISO") (class "Default")
      (node (ref "M1") (pin "59") (pinfunction "SPI0-MISO/PC1_59") (pintype "passive"))
    )
    (net (code "76") (name "/SPI0-MOSI") (class "Default")
      (node (ref "M1") (pin "60") (pinfunction "SPI0-MOSI/PC0_60") (pintype "passive"))
    )
    (net (code "77") (name "/T-CARD-DET") (class "Default")
      (node (ref "J9") (pin "10") (pinfunction "CD#_10") (pintype "passive"))
      (node (ref "M1") (pin "52") (pinfunction "T-CARD-DET/PB4_52") (pintype "passive"))
    )
    (net (code "78") (name "/TP-INT") (class "Default")
      (node (ref "J3") (pin "37") (pinfunction "37_37") (pintype "passive"))
      (node (ref "M1") (pin "34") (pinfunction "TP-INT/PB5_34") (pintype "passive"))
    )
    (net (code "79") (name "/TP-RST") (class "Default")
      (node (ref "J3") (pin "40") (pinfunction "40_40") (pintype "passive"))
      (node (ref "M1") (pin "31") (pinfunction "TP-RST/PH1_31") (pintype "passive"))
    )
    (net (code "80") (name "/TP-SCK") (class "Default")
      (node (ref "J3") (pin "39") (pinfunction "39_39") (pintype "passive"))
      (node (ref "M1") (pin "32") (pinfunction "TP-SCK/PH2_32") (pintype "passive"))
      (node (ref "R8") (pin "2") (pinfunction "2_2") (pintype "passive"))
    )
    (net (code "81") (name "/TP-SDA") (class "Default")
      (node (ref "J3") (pin "38") (pinfunction "38_38") (pintype "passive"))
      (node (ref "M1") (pin "33") (pinfunction "TP-SDA/PH3_33") (pintype "passive"))
      (node (ref "R7") (pin "2") (pinfunction "2_2") (pintype "passive"))
    )
    (net (code "82") (name "/Temp") (class "Default")
      (node (ref "C50") (pin "1") (pinfunction "1_1") (pintype "passive"))
      (node (ref "M1") (pin "5") (pinfunction "TS_5") (pintype "passive"))
      (node (ref "R76") (pin "2") (pinfunction "2_2") (pintype "passive"))
      (node (ref "RT1") (pin "1") (pinfunction "1_1") (pintype "passive"))
    )
    (net (code "83") (name "/USB-DM0") (class "Default")
      (node (ref "D22") (pin "2") (pinfunction "K_2") (pintype "passive"))
      (node (ref "J10") (pin "2") (pinfunction "D-_2") (pintype "passive"))
      (node (ref "M1") (pin "113") (pinfunction "USB-DM0_113") (pintype "passive"))
    )
    (net (code "84") (name "/USB-DM1") (class "Default")
      (node (ref "D11") (pin "2") (pinfunction "K_2") (pintype "passive"))
      (node (ref "J11") (pin "2") (pinfunction "D-_2") (pintype "passive"))
      (node (ref "R110") (pin "2") (pinfunction "2_2") (pintype "passive"))
      (node (ref "R113") (pin "2") (pinfunction "2_2") (pintype "passive"))
    )
    (net (code "85") (name "/USB-DP0") (class "Default")
      (node (ref "D21") (pin "2") (pinfunction "K_2") (pintype "passive"))
      (node (ref "J10") (pin "3") (pinfunction "D+_3") (pintype "passive"))
      (node (ref "M1") (pin "114") (pinfunction "USB-DP0_114") (pintype "passive"))
    )
    (net (code "86") (name "/USB-DP1") (class "Default")
      (node (ref "D12") (pin "2") (pinfunction "K_2") (pintype "passive"))
      (node (ref "J11") (pin "3") (pinfunction "D+_3") (pintype "passive"))
      (node (ref "R111") (pin "2") (pinfunction "2_2") (pintype "passive"))
      (node (ref "R112") (pin "2") (pinfunction "2_2") (pintype "passive"))
    )
    (net (code "87") (name "/USB-DRVVBUS") (class "Default")
      (node (ref "M1") (pin "21") (pinfunction "USB-DRVVBUS_21") (pintype "passive"))
    )
    (net (code "88") (name "/USB-ID") (class "Default")
      (node (ref "M1") (pin "29") (pinfunction "USB-ID/PH8_29") (pintype "passive"))
      (node (ref "R70") (pin "1") (pinfunction "1_1") (pintype "passive"))
    )
    (net (code "89") (name "/WL-HOST-WAKE") (class "Default")
      (node (ref "M1") (pin "108") (pinfunction "WL-WAKE-AP/PL7_108") (pintype "passive"))
      (node (ref "U7") (pin "13") (pinfunction "WL_HOST_WAKE_13") (pintype "passive"))
    )
    (net (code "90") (name "/WL-REG-ON") (class "Default")
      (node (ref "M1") (pin "107") (pinfunction "WL-PMU-EN/PL6_107") (pintype "passive"))
      (node (ref "R82") (pin "1") (pinfunction "1_1") (pintype "passive"))
      (node (ref "U7") (pin "12") (pinfunction "WL_REG_ON_12") (pintype "passive"))
    )
    (net (code "91") (name "AVDD-CSI") (class "Default")
      (node (ref "C29") (pin "1") (pinfunction "1_1") (pintype "passive"))
      (node (ref "J2") (pin "3") (pinfunction "3_3") (pintype "passive"))
      (node (ref "M1") (pin "8") (pinfunction "AVDD-CSI_8") (pintype "passive"))
    )
    (net (code "92") (name "DOVDD-CSI") (class "Default")
      (node (ref "C23") (pin "1") (pinfunction "1_1") (pintype "passive"))
      (node (ref "C24") (pin "1") (pinfunction "1_1") (pintype "passive"))
      (node (ref "C25") (pin "1") (pinfunction "1_1") (pintype "passive"))
      (node (ref "J2") (pin "10") (pinfunction "10_10") (pintype "passive"))
      (node (ref "M1") (pin "2") (pinfunction "DOVDD-CSI_2") (pintype "passive"))
      (node (ref "R39") (pin "2") (pinfunction "2_2") (pintype "passive"))
      (node (ref "R50") (pin "1") (pinfunction "1_1") (pintype "passive"))
    )
    (net (code "93") (name "DVDD1V8-CSI") (class "Default")
      (node (ref "C28") (pin "1") (pinfunction "1_1") (pintype "passive"))
      (node (ref "J2") (pin "9") (pinfunction "9_9") (pintype "passive"))
      (node (ref "M1") (pin "13") (pinfunction "DVDD1V8-CSI_13") (pintype "passive"))
    )
    (net (code "94") (name "GND") (class "Default")
      (node (ref "ANT1") (pin "2") (pinfunction "2_2") (pintype "passive"))
      (node (ref "ANT1") (pin "3") (pinfunction "3_3") (pintype "passive"))
      (node (ref "C102") (pin "2") (pinfunction "2_2") (pintype "passive"))
      (node (ref "C103") (pin "1") (pinfunction "1_1") (pintype "passive"))
      (node (ref "C104") (pin "2") (pinfunction "2_2") (pintype "passive"))
      (node (ref "C105") (pin "1") (pinfunction "1_1") (pintype "passive"))
      (node (ref "C110") (pin "2") (pinfunction "2_2") (pintype "passive"))
      (node (ref "C23") (pin "2") (pinfunction "2_2") (pintype "passive"))
      (node (ref "C24") (pin "2") (pinfunction "2_2") (pintype "passive"))
      (node (ref "C25") (pin "2") (pinfunction "2_2") (pintype "passive"))
      (node (ref "C28") (pin "2") (pinfunction "2_2") (pintype "passive"))
      (node (ref "C29") (pin "2") (pinfunction "2_2") (pintype "passive"))
      (node (ref "C32") (pin "1") (pinfunction "1_1") (pintype "passive"))
      (node (ref "C33") (pin "1") (pinfunction "1_1") (pintype "passive"))
      (node (ref "C34") (pin "2") (pinfunction "2_2") (pintype "passive"))
      (node (ref "C35") (pin "1") (pinfunction "1_1") (pintype "passive"))
      (node (ref "C36") (pin "2") (pinfunction "2_2") (pintype "passive"))
      (node (ref "C37") (pin "1") (pinfunction "1_1") (pintype "passive"))
      (node (ref "C39") (pin "2") (pinfunction "2_2") (pintype "passive"))
      (node (ref "C40") (pin "2") (pinfunction "2_2") (pintype "passive"))
      (node (ref "C41") (pin "2") (pinfunction "2_2") (pintype "passive"))
      (node (ref "C42") (pin "2") (pinfunction "2_2") (pintype "passive"))
      (node (ref "C43") (pin "2") (pinfunction "2_2") (pintype "passive"))
      (node (ref "C44") (pin "1") (pinfunction "1_1") (pintype "passive"))
      (node (ref "C45") (pin "2") (pinfunction "2_2") (pintype "passive"))
      (node (ref "C47") (pin "1") (pinfunction "1_1") (pintype "passive"))
      (node (ref "C48") (pin "1") (pinfunction "1_1") (pintype "passive"))
      (node (ref "C50") (pin "2") (pinfunction "2_2") (pintype "passive"))
      (node (ref "C51") (pin "2") (pinfunction "2_2") (pintype "passive"))
      (node (ref "C55") (pin "1") (pinfunction "1_1") (pintype "passive"))
      (node (ref "C56") (pin "1") (pinfunction "1_1") (pintype "passive"))
      (node (ref "C57") (pin "2") (pinfunction "2_2") (pintype "passive"))
      (node (ref "D11") (pin "1") (pinfunction "A_1") (pintype "passive"))
      (node (ref "D12") (pin "1") (pinfunction "A_1") (pintype "passive"))
      (node (ref "D21") (pin "1") (pinfunction "A_1") (pintype "passive"))
      (node (ref "D22") (pin "1") (pinfunction "A_1") (pintype "passive"))
      (node (ref "D7") (pin "K") (pintype "passive"))
      (node (ref "J1") (pin "1") (pinfunction "1_1") (pintype "passive"))
      (node (ref "J1") (pin "12") (pinfunction "12_12") (pintype "passive"))
      (node (ref "J1") (pin "13") (pinfunction "13_13") (pintype "passive"))
      (node (ref "J1") (pin "14") (pinfunction "14_14") (pintype "passive"))
      (node (ref "J1") (pin "9") (pinfunction "9_9") (pintype "passive"))
      (node (ref "J10") (pin "10") (pinfunction "SHELL_10") (pintype "passive"))
      (node (ref "J10") (pin "5") (pinfunction "GND_5") (pintype "passive"))
      (node (ref "J10") (pin "6") (pinfunction "SHELL_6") (pintype "passive"))
      (node (ref "J10") (pin "7") (pinfunction "SHELL_7") (pintype "passive"))
      (node (ref "J10") (pin "8") (pinfunction "SHELL_8") (pintype "passive"))
      (node (ref "J10") (pin "9") (pinfunction "SHELL_9") (pintype "passive"))
      (node (ref "J11") (pin "10") (pinfunction "SHELL_10") (pintype "passive"))
      (node (ref "J11") (pin "5") (pinfunction "GND_5") (pintype "passive"))
      (node (ref "J11") (pin "6") (pinfunction "SHELL_6") (pintype "passive"))
      (node (ref "J11") (pin "7") (pinfunction "SHELL_7") (pintype "passive"))
      (node (ref "J11") (pin "8") (pinfunction "SHELL_8") (pintype "passive"))
      (node (ref "J11") (pin "9") (pinfunction "SHELL_9") (pintype "passive"))
      (node (ref "J2") (pin "1") (pinfunction "1_1") (pintype "passive"))
      (node (ref "J2") (pin "12") (pinfunction "12_12") (pintype "passive"))
      (node (ref "J2") (pin "13") (pinfunction "13_13") (pintype "passive"))
      (node (ref "J2") (pin "14") (pinfunction "14_14") (pintype "passive"))
      (node (ref "J3") (pin "34") (pinfunction "34_34") (pintype "passive"))
      (node (ref "J3") (pin "41") (pinfunction "41_41") (pintype "passive"))
      (node (ref "J3") (pin "42") (pinfunction "42_42") (pintype "passive"))
      (node (ref "J3") (pin "5") (pinfunction "5_5") (pintype "passive"))
      (node (ref "J3") (pin "6") (pinfunction "6_6") (pintype "passive"))
      (node (ref "J3") (pin "9") (pinfunction "9_9") (pintype "passive"))
      (node (ref "J6") (pin "3") (pinfunction "3_3") (pintype "passive"))
      (node (ref "J6") (pin "4") (pinfunction "4_4") (pintype "passive"))
      (node (ref "J7") (pin "3") (pinfunction "3_3") (pintype "passive"))
      (node (ref "J7") (pin "4") (pinfunction "4_4") (pintype "passive"))
      (node (ref "J8") (pin "2") (pinfunction "2_2") (pintype "passive"))
      (node (ref "J9") (pin "11") (pinfunction "GND_11") (pintype "passive"))
      (node (ref "J9") (pin "12") (pinfunction "GND_12") (pintype "passive"))
      (node (ref "J9") (pin "7") (pinfunction "VSS2_7") (pintype "passive"))
      (node (ref "M1") (pin "103") (pinfunction "GND_103") (pintype "passive"))
      (node (ref "M1") (pin "121") (pinfunction "GND_121") (pintype "passive"))
      (node (ref "M1") (pin "122") (pinfunction "GND_122") (pintype "passive"))
      (node (ref "M1") (pin "123") (pinfunction "GND_123") (pintype "passive"))
      (node (ref "M1") (pin "124") (pinfunction "GND_124") (pintype "passive"))
      (node (ref "M1") (pin "40") (pinfunction "GND_40") (pintype "passive"))
      (node (ref "M1") (pin "51") (pinfunction "GND_51") (pintype "passive"))
      (node (ref "M1") (pin "9") (pinfunction "GND_9") (pintype "passive"))
      (node (ref "R102") (pin "1") (pinfunction "1_1") (pintype "passive"))
      (node (ref "R104") (pin "1") (pinfunction "1_1") (pintype "passive"))
      (node (ref "R74") (pin "2") (pinfunction "2_2") (pintype "passive"))
      (node (ref "R76") (pin "1") (pinfunction "1_1") (pintype "passive"))
      (node (ref "R77") (pin "2") (pinfunction "2_2") (pintype "passive"))
      (node (ref "R82") (pin "2") (pinfunction "2_2") (pintype "passive"))
      (node (ref "S1") (pin "1") (pinfunction "1_1") (pintype "passive"))
      (node (ref "U10") (pin "2") (pinfunction "GND_2") (pintype "passive"))
      (node (ref "U4") (pin "2") (pinfunction "GND_2") (pintype "passive"))
      (node (ref "U5") (pin "8") (pinfunction "GND_8") (pintype "passive"))
      (node (ref "U7") (pin "1") (pinfunction "GND_1") (pintype "passive"))
      (node (ref "U7") (pin "20") (pinfunction "GND_20") (pintype "passive"))
      (node (ref "U7") (pin "3") (pinfunction "GND_3") (pintype "passive"))
      (node (ref "U7") (pin "31") (pinfunction "GND_31") (pintype "passive"))
      (node (ref "U7") (pin "33") (pinfunction "GND_33") (pintype "passive"))
      (node (ref "U7") (pin "36") (pinfunction "GND_36") (pintype "passive"))
      (node (ref "Y1") (pin "2") (pinfunction "GND_2") (pintype "passive"))
      (node (ref "Y1") (pin "4") (pinfunction "GND_4") (pintype "passive"))
    )
    (net (code "95") (name "Net-(ANT1-W)") (class "Default")
      (node (ref "ANT1") (pin "1") (pinfunction "W_1") (pintype "passive"))
      (node (ref "C47") (pin "2") (pinfunction "2_2") (pintype "passive"))
      (node (ref "C49") (pin "2") (pinfunction "2_2") (pintype "passive"))
    )
    (net (code "96") (name "Net-(C36-Pad1)") (class "Default")
      (node (ref "C36") (pin "1") (pinfunction "1_1") (pintype "passive"))
      (node (ref "J6") (pin "2") (pinfunction "2_2") (pintype "passive"))
      (node (ref "L3") (pin "1") (pinfunction "1_1") (pintype "passive"))
    )
    (net (code "97") (name "Net-(C40-Pad1)") (class "Default")
      (node (ref "C40") (pin "1") (pinfunction "1_1") (pintype "passive"))
      (node (ref "J6") (pin "1") (pinfunction "1_1") (pintype "passive"))
      (node (ref "L4") (pin "1") (pinfunction "1_1") (pintype "passive"))
    )
    (net (code "98") (name "Net-(C100-Pad2)") (class "Default")
      (node (ref "C100") (pin "2") (pinfunction "2_2") (pintype "passive"))
      (node (ref "R66") (pin "1") (pinfunction "1_1") (pintype "passive"))
    )
    (net (code "99") (name "Net-(C101-Pad2)") (class "Default")
      (node (ref "C101") (pin "2") (pinfunction "2_2") (pintype "passive"))
      (node (ref "R67") (pin "1") (pinfunction "1_1") (pintype "passive"))
    )
    (net (code "100") (name "Net-(D6-PadK)") (class "Default")
      (node (ref "D6") (pin "K") (pintype "passive"))
      (node (ref "R83") (pin "1") (pinfunction "1_1") (pintype "passive"))
    )
    (net (code "101") (name "Net-(D7-PadA)") (class "Default")
      (node (ref "D7") (pin "A") (pintype "passive"))
      (node (ref "R92") (pin "1") (pinfunction "1_1") (pintype "passive"))
    )
    (net (code "102") (name "Net-(J9-Voice_Key)") (class "Default")
      (node (ref "J9") (pin "1") (pinfunction "Voice_Key_1") (pintype "passive"))
      (node (ref "R69") (pin "2") (pinfunction "2_2") (pintype "passive"))
    )
    (net (code "103") (name "Net-(J10-ID)") (class "Default")
      (node (ref "J10") (pin "4") (pinfunction "ID_4") (pintype "passive"))
      (node (ref "R70") (pin "2") (pinfunction "2_2") (pintype "passive"))
      (node (ref "R71") (pin "1") (pinfunction "1_1") (pintype "passive"))
    )
    (net (code "104") (name "Net-(J11-ID)") (class "Default")
      (node (ref "J11") (pin "4") (pinfunction "ID_4") (pintype "passive"))
      (node (ref "R120") (pin "2") (pinfunction "2_2") (pintype "passive"))
    )
    (net (code "105") (name "Net-(M1-USB-DM1)") (class "Default")
      (node (ref "M1") (pin "111") (pinfunction "USB-DM1_111") (pintype "passive"))
      (node (ref "R113") (pin "1") (pinfunction "1_1") (pintype "passive"))
    )
    (net (code "106") (name "Net-(M1-USB-DP1)") (class "Default")
      (node (ref "M1") (pin "112") (pinfunction "USB-DP1_112") (pintype "passive"))
      (node (ref "R112") (pin "1") (pinfunction "1_1") (pintype "passive"))
    )
    (net (code "107") (name "Net-(U4-IN_A1)") (class "Default")
      (node (ref "R62") (pin "1") (pinfunction "1_1") (pintype "passive"))
      (node (ref "R65") (pin "2") (pinfunction "2_2") (pintype "passive"))
      (node (ref "U4") (pin "1") (pinfunction "IN_A1_1") (pintype "passive"))
      (node (ref "U4") (pin "4") (pinfunction "OUT_Y2_4") (pintype "passive"))
    )
    (net (code "108") (name "Net-(U4-IN_A2)") (class "Default")
      (node (ref "C45") (pin "1") (pinfunction "1_1") (pintype "passive"))
      (node (ref "R65") (pin "1") (pinfunction "1_1") (pintype "passive"))
      (node (ref "U4") (pin "3") (pinfunction "IN_A2_3") (pintype "passive"))
      (node (ref "Y1") (pin "3") (pinfunction "XO_3") (pintype "passive"))
    )
    (net (code "109") (name "Net-(U4-OUT_Y1)") (class "Default")
      (node (ref "R63") (pin "2") (pinfunction "2_2") (pintype "passive"))
      (node (ref "U4") (pin "6") (pinfunction "OUT_Y1_6") (pintype "passive"))
    )
    (net (code "110") (name "Net-(U4-VCC)") (class "Default")
      (node (ref "R64") (pin "2") (pinfunction "2_2") (pintype "passive"))
      (node (ref "U4") (pin "5") (pinfunction "VCC_5") (pintype "passive"))
    )
    (net (code "111") (name "Net-(U5-IN+)") (class "Default")
      (node (ref "R67") (pin "2") (pinfunction "2_2") (pintype "passive"))
      (node (ref "U5") (pin "3") (pinfunction "IN+_3") (pintype "passive"))
    )
    (net (code "112") (name "Net-(U5-IN-)") (class "Default")
      (node (ref "R66") (pin "2") (pinfunction "2_2") (pintype "passive"))
      (node (ref "U5") (pin "4") (pinfunction "IN-_4") (pintype "passive"))
    )
    (net (code "113") (name "Net-(U5-OUT+)") (class "Default")
      (node (ref "L3") (pin "2") (pinfunction "2_2") (pintype "passive"))
      (node (ref "U5") (pin "7") (pinfunction "OUT+_7") (pintype "passive"))
    )
    (net (code "114") (name "Net-(U5-OUT-)") (class "Default")
      (node (ref "L4") (pin "2") (pinfunction "2_2") (pintype "passive"))
      (node (ref "U5") (pin "6") (pinfunction "OUT-_6") (pintype "passive"))
    )
    (net (code "115") (name "Net-(U7-LPO)") (class "Default")
      (node (ref "R79") (pin "1") (pinfunction "1_1") (pintype "passive"))
      (node (ref "U7") (pin "24") (pinfunction "LPO_24") (pintype "passive"))
    )
    (net (code "116") (name "Net-(U7-SDIO_DATA_CLK)") (class "Default")
      (node (ref "R84") (pin "1") (pinfunction "1_1") (pintype "passive"))
      (node (ref "U7") (pin "17") (pinfunction "SDIO_DATA_CLK_17") (pintype "passive"))
    )
    (net (code "117") (name "Net-(U7-VIN_LDO)") (class "Default")
      (node (ref "C56") (pin "2") (pinfunction "2_2") (pintype "passive"))
      (node (ref "L2") (pin "2") (pinfunction "2_2") (pintype "passive"))
      (node (ref "U7") (pin "23") (pinfunction "VIN_LDO_23") (pintype "passive"))
    )
    (net (code "118") (name "Net-(U7-VIN_LDO_OUT)") (class "Default")
      (node (ref "L2") (pin "1") (pinfunction "1_1") (pintype "passive"))
      (node (ref "U7") (pin "21") (pinfunction "VIN_LDO_OUT_21") (pintype "passive"))
    )
    (net (code "119") (name "Net-(U7-WL_BT_ANT)") (class "Default")
      (node (ref "C48") (pin "2") (pinfunction "2_2") (pintype "passive"))
      (node (ref "C49") (pin "1") (pinfunction "1_1") (pintype "passive"))
      (node (ref "U7") (pin "2") (pinfunction "WL_BT_ANT_2") (pintype "passive"))
    )
    (net (code "120") (name "Net-(U7-WL_VDD_TCXO)") (class "Default")
      (node (ref "R75") (pin "1") (pinfunction "1_1") (pintype "passive"))
      (node (ref "U7") (pin "29") (pinfunction "WL_VDD_TCXO_29") (pintype "passive"))
    )
    (net (code "121") (name "Net-(U10-EN)") (class "Default")
      (node (ref "R101") (pin "2") (pinfunction "2_2") (pintype "passive"))
      (node (ref "R102") (pin "2") (pinfunction "2_2") (pintype "passive"))
      (node (ref "U10") (pin "4") (pinfunction "EN_4") (pintype "passive"))
    )
    (net (code "122") (name "Net-(U10-FB)") (class "Default")
      (node (ref "R103") (pin "1") (pinfunction "1_1") (pintype "passive"))
      (node (ref "R104") (pin "2") (pinfunction "2_2") (pintype "passive"))
      (node (ref "U10") (pin "3") (pinfunction "FB_3") (pintype "passive"))
    )
    (net (code "123") (name "Net-(U10-LX)") (class "Default")
      (node (ref "L1") (pin "2") (pinfunction "2_2") (pintype "passive"))
      (node (ref "U10") (pin "1") (pinfunction "LX_1") (pintype "passive"))
    )
    (net (code "124") (name "Net-(Y1-XI)") (class "Default")
      (node (ref "C34") (pin "1") (pinfunction "1_1") (pintype "passive"))
      (node (ref "R62") (pin "2") (pinfunction "2_2") (pintype "passive"))
      (node (ref "Y1") (pin "1") (pinfunction "XI_1") (pintype "passive"))
    )
    (net (code "125") (name "PS") (class "Default")
      (node (ref "C102") (pin "1") (pinfunction "1_1") (pintype "passive"))
      (node (ref "C103") (pin "2") (pinfunction "2_2") (pintype "passive"))
      (node (ref "D6") (pin "A") (pintype "passive"))
      (node (ref "L1") (pin "1") (pinfunction "1_1") (pintype "passive"))
      (node (ref "M1") (pin "10") (pinfunction "PS_10") (pintype "passive"))
      (node (ref "M1") (pin "11") (pinfunction "PS_11") (pintype "passive"))
      (node (ref "U10") (pin "6") (pinfunction "IN_6") (pintype "passive"))
    )
    (net (code "126") (name "USBVBUS") (class "Default")
      (node (ref "C42") (pin "1") (pinfunction "1_1") (pintype "passive"))
      (node (ref "C43") (pin "1") (pinfunction "1_1") (pintype "passive"))
      (node (ref "C44") (pin "2") (pinfunction "2_2") (pintype "passive"))
      (node (ref "J10") (pin "1") (pinfunction "VCC_1") (pintype "passive"))
      (node (ref "M1") (pin "12") (pinfunction "USBVBUS_12") (pintype "passive"))
    )
    (net (code "127") (name "VBAT") (class "Default")
      (node (ref "C41") (pin "1") (pinfunction "1_1") (pintype "passive"))
      (node (ref "J8") (pin "1") (pinfunction "1_1") (pintype "passive"))
      (node (ref "M1") (pin "19") (pinfunction "VBAT_19") (pintype "passive"))
      (node (ref "M1") (pin "20") (pinfunction "VBAT_20") (pintype "passive"))
    )
    (net (code "128") (name "VCC-3V0") (class "Default")
      (node (ref "C110") (pin "1") (pinfunction "1_1") (pintype "passive"))
      (node (ref "C32") (pin "2") (pinfunction "2_2") (pintype "passive"))
      (node (ref "C33") (pin "2") (pinfunction "2_2") (pintype "passive"))
      (node (ref "C37") (pin "2") (pinfunction "2_2") (pintype "passive"))
      (node (ref "J9") (pin "5") (pinfunction "VDD_5") (pintype "passive"))
      (node (ref "M1") (pin "1") (pinfunction "VCC-3V0_1") (pintype "passive"))
      (node (ref "R101") (pin "1") (pinfunction "1_1") (pintype "passive"))
      (node (ref "R68") (pin "1") (pinfunction "1_1") (pintype "passive"))
      (node (ref "R71") (pin "2") (pinfunction "2_2") (pintype "passive"))
      (node (ref "R92") (pin "2") (pinfunction "2_2") (pintype "passive"))
      (node (ref "U5") (pin "1") (pinfunction "SD_1") (pintype "passive"))
      (node (ref "U5") (pin "2") (pinfunction "ABD_2") (pintype "passive"))
      (node (ref "U5") (pin "5") (pinfunction "VDD_5") (pintype "passive"))
    )
    (net (code "129") (name "VCC-CTP") (class "Default")
      (node (ref "J3") (pin "35") (pinfunction "35_35") (pintype "passive"))
      (node (ref "J3") (pin "36") (pinfunction "36_36") (pintype "passive"))
      (node (ref "M1") (pin "6") (pinfunction "VCC-CTP_6") (pintype "passive"))
      (node (ref "R7") (pin "1") (pinfunction "1_1") (pintype "passive"))
      (node (ref "R8") (pin "1") (pinfunction "1_1") (pintype "passive"))
    )
    (net (code "130") (name "VCC-LCD") (class "Default")
      (node (ref "J3") (pin "7") (pinfunction "7_7") (pintype "passive"))
      (node (ref "J3") (pin "8") (pinfunction "8_8") (pintype "passive"))
      (node (ref "M1") (pin "4") (pinfunction "VCC-LCD_4") (pintype "passive"))
      (node (ref "RT1") (pin "2") (pinfunction "2_2") (pintype "passive"))
    )
    (net (code "131") (name "VCC-WIFI") (class "Default")
      (node (ref "C51") (pin "1") (pinfunction "1_1") (pintype "passive"))
      (node (ref "C55") (pin "2") (pinfunction "2_2") (pintype "passive"))
      (node (ref "C57") (pin "1") (pinfunction "1_1") (pintype "passive"))
      (node (ref "M1") (pin "3") (pinfunction "VCC-IO-WIFI_3") (pintype "passive"))
      (node (ref "R64") (pin "1") (pinfunction "1_1") (pintype "passive"))
      (node (ref "R72") (pin "1") (pinfunction "1_1") (pintype "passive"))
      (node (ref "R73") (pin "1") (pinfunction "1_1") (pintype "passive"))
      (node (ref "R75") (pin "2") (pinfunction "2_2") (pintype "passive"))
      (node (ref "R80") (pin "1") (pinfunction "1_1") (pintype "passive"))
      (node (ref "R87") (pin "1") (pinfunction "1_1") (pintype "passive"))
      (node (ref "R88") (pin "1") (pinfunction "1_1") (pintype "passive"))
      (node (ref "R89") (pin "1") (pinfunction "1_1") (pintype "passive"))
      (node (ref "R90") (pin "1") (pinfunction "1_1") (pintype "passive"))
      (node (ref "R91") (pin "1") (pinfunction "1_1") (pintype "passive"))
      (node (ref "U7") (pin "22") (pinfunction "VDDIO_22") (pintype "passive"))
      (node (ref "U7") (pin "9") (pinfunction "VBAT_9") (pintype "passive"))
    )
    (net (code "132") (name "unconnected-(M1-ACIN5V-Pad15)") (class "Default")
      (node (ref "M1") (pin "15") (pinfunction "ACIN5V_15") (pintype "passive"))
    )
    (net (code "133") (name "unconnected-(M1-ACIN5V-Pad16)") (class "Default")
      (node (ref "M1") (pin "16") (pinfunction "ACIN5V_16") (pintype "passive"))
    )
    (net (code "134") (name "unconnected-(M1-NC-Pad125)") (class "Default")
      (node (ref "M1") (pin "125") (pinfunction "NC_125") (pintype "passive"))
    )
    (net (code "135") (name "unconnected-(M1-NC-Pad126)") (class "Default")
      (node (ref "M1") (pin "126") (pinfunction "NC_126") (pintype "passive"))
    )
    (net (code "136") (name "unconnected-(M1-PA-SHDN{slash}PH9-Pad39)") (class "Default")
      (node (ref "M1") (pin "39") (pinfunction "PA-SHDN/PH9_39") (pintype "passive"))
    )
    (net (code "137") (name "unconnected-(M1-PE14_CSI-RST-R-Pad77)") (class "Default")
      (node (ref "M1") (pin "77") (pinfunction "PE14_CSI-RST-R_77") (pintype "passive"))
    )
    (net (code "138") (name "unconnected-(M1-PE15_CSI-STBY-R-Pad78)") (class "Default")
      (node (ref "M1") (pin "78") (pinfunction "PE15_CSI-STBY-R_78") (pintype "passive"))
    )
    (net (code "139") (name "unconnected-(M1-PL11-Pad104)") (class "Default")
      (node (ref "M1") (pin "104") (pinfunction "PL11_104") (pintype "passive"))
    )
    (net (code "140") (name "unconnected-(M1-RESET-N-Pad22)") (class "Default")
      (node (ref "M1") (pin "22") (pinfunction "RESET-N_22") (pintype "passive"))
    )
    (net (code "141") (name "unconnected-(M1-UART2-CTS{slash}PB3-Pad25)") (class "Default")
      (node (ref "M1") (pin "25") (pinfunction "UART2-CTS/PB3_25") (pintype "passive"))
    )
    (net (code "142") (name "unconnected-(M1-UART2-RTS{slash}PB2-Pad26)") (class "Default")
      (node (ref "M1") (pin "26") (pinfunction "UART2-RTS/PB2_26") (pintype "passive"))
    )
    (net (code "143") (name "unconnected-(M1-UART2-RX{slash}PB1-Pad23)") (class "Default")
      (node (ref "M1") (pin "23") (pinfunction "UART2-RX/PB1_23") (pintype "passive"))
    )
    (net (code "144") (name "unconnected-(M1-UART2-TX{slash}PB0-Pad24)") (class "Default")
      (node (ref "M1") (pin "24") (pinfunction "UART2-TX/PB0_24") (pintype "passive"))
    )
    (net (code "145") (name "unconnected-(M1-UART3-RX{slash}PH7-Pad27)") (class "Default")
      (node (ref "M1") (pin "27") (pinfunction "UART3-RX/PH7_27") (pintype "passive"))
    )
    (net (code "146") (name "unconnected-(M1-UART3-TX{slash}PH6-Pad28)") (class "Default")
      (node (ref "M1") (pin "28") (pinfunction "UART3-TX/PH6_28") (pintype "passive"))
    )
    (net (code "147") (name "unconnected-(M1-VBAT-EXT-Pad17)") (class "Default")
      (node (ref "M1") (pin "17") (pinfunction "VBAT-EXT_17") (pintype "passive"))
    )
    (net (code "148") (name "unconnected-(M1-VBAT-EXT-Pad18)") (class "Default")
      (node (ref "M1") (pin "18") (pinfunction "VBAT-EXT_18") (pintype "passive"))
    )
    (net (code "149") (name "unconnected-(M1-VCC-RTC-Pad7)") (class "Default")
      (node (ref "M1") (pin "7") (pinfunction "VCC-RTC_7") (pintype "passive"))
    )
    (net (code "150") (name "unconnected-(U7-BT_XTAL_IN-Pad37)") (class "Default")
      (node (ref "U7") (pin "37") (pinfunction "BT_XTAL_IN_37") (pintype "passive"))
    )
    (net (code "151") (name "unconnected-(U7-BT_XTAL_OUT-Pad38)") (class "Default")
      (node (ref "U7") (pin "38") (pinfunction "BT_XTAL_OUT_38") (pintype "passive"))
    )
    (net (code "152") (name "unconnected-(U7-NC-Pad4)") (class "Default")
      (node (ref "U7") (pin "4") (pinfunction "NC_4") (pintype "passive"))
    )
    (net (code "153") (name "unconnected-(U7-NC-Pad5)") (class "Default")
      (node (ref "U7") (pin "5") (pinfunction "NC_5") (pintype "passive"))
    )
    (net (code "154") (name "unconnected-(U7-NC-Pad8)") (class "Default")
      (node (ref "U7") (pin "8") (pinfunction "NC_8") (pintype "passive"))
    )
    (net (code "155") (name "unconnected-(U7-NC-Pad10)") (class "Default")
      (node (ref "U7") (pin "10") (pinfunction "NC_10") (pintype "passive"))
    )
    (net (code "156") (name "unconnected-(U7-NC-Pad11)") (class "Default")
      (node (ref "U7") (pin "11") (pinfunction "NC_11") (pintype "passive"))
    )
    (net (code "157") (name "unconnected-(U7-NC-Pad32)") (class "Default")
      (node (ref "U7") (pin "32") (pinfunction "NC_32") (pintype "passive"))
    )
    (net (code "158") (name "unconnected-(U7-NC-Pad35)") (class "Default")
      (node (ref "U7") (pin "35") (pinfunction "NC_35") (pintype "passive"))
    )
    (net (code "159") (name "unconnected-(U7-NC-Pad39)") (class "Default")
      (node (ref "U7") (pin "39") (pinfunction "NC_39") (pintype "passive"))
    )
    (net (code "160") (name "unconnected-(U7-NC-Pad40)") (class "Default")
      (node (ref "U7") (pin "40") (pinfunction "NC_40") (pintype "passive"))
    )
    (net (code "161") (name "unconnected-(U7-NC-Pad45)") (class "Default")
      (node (ref "U7") (pin "45") (pinfunction "NC_45") (pintype "passive"))
    )
    (net (code "162") (name "unconnected-(U7-NC-Pad46)") (class "Default")
      (node (ref "U7") (pin "46") (pinfunction "NC_46") (pintype "passive"))
    )
    (net (code "163") (name "unconnected-(U7-NC-Pad47)") (class "Default")
      (node (ref "U7") (pin "47") (pinfunction "NC_47") (pintype "passive"))
    )
    (net (code "164") (name "unconnected-(U7-PCM_CLK-Pad26)") (class "Default")
      (node (ref "U7") (pin "26") (pinfunction "PCM_CLK_26") (pintype "passive"))
    )
    (net (code "165") (name "unconnected-(U7-PCM_IN-Pad27)") (class "Default")
      (node (ref "U7") (pin "27") (pinfunction "PCM_IN_27") (pintype "passive"))
    )
    (net (code "166") (name "unconnected-(U7-PCM_OUT-Pad25)") (class "Default")
      (node (ref "U7") (pin "25") (pinfunction "PCM_OUT_25") (pintype "passive"))
    )
    (net (code "167") (name "unconnected-(U7-PCM_SYNC-Pad28)") (class "Default")
      (node (ref "U7") (pin "28") (pinfunction "PCM_SYNC_28") (pintype "passive"))
    )
  )
)
